# xadow-3-Axis_Digital_Accelerometer_400g.net
KiCad netlist of a schematic drawn in EAGLE
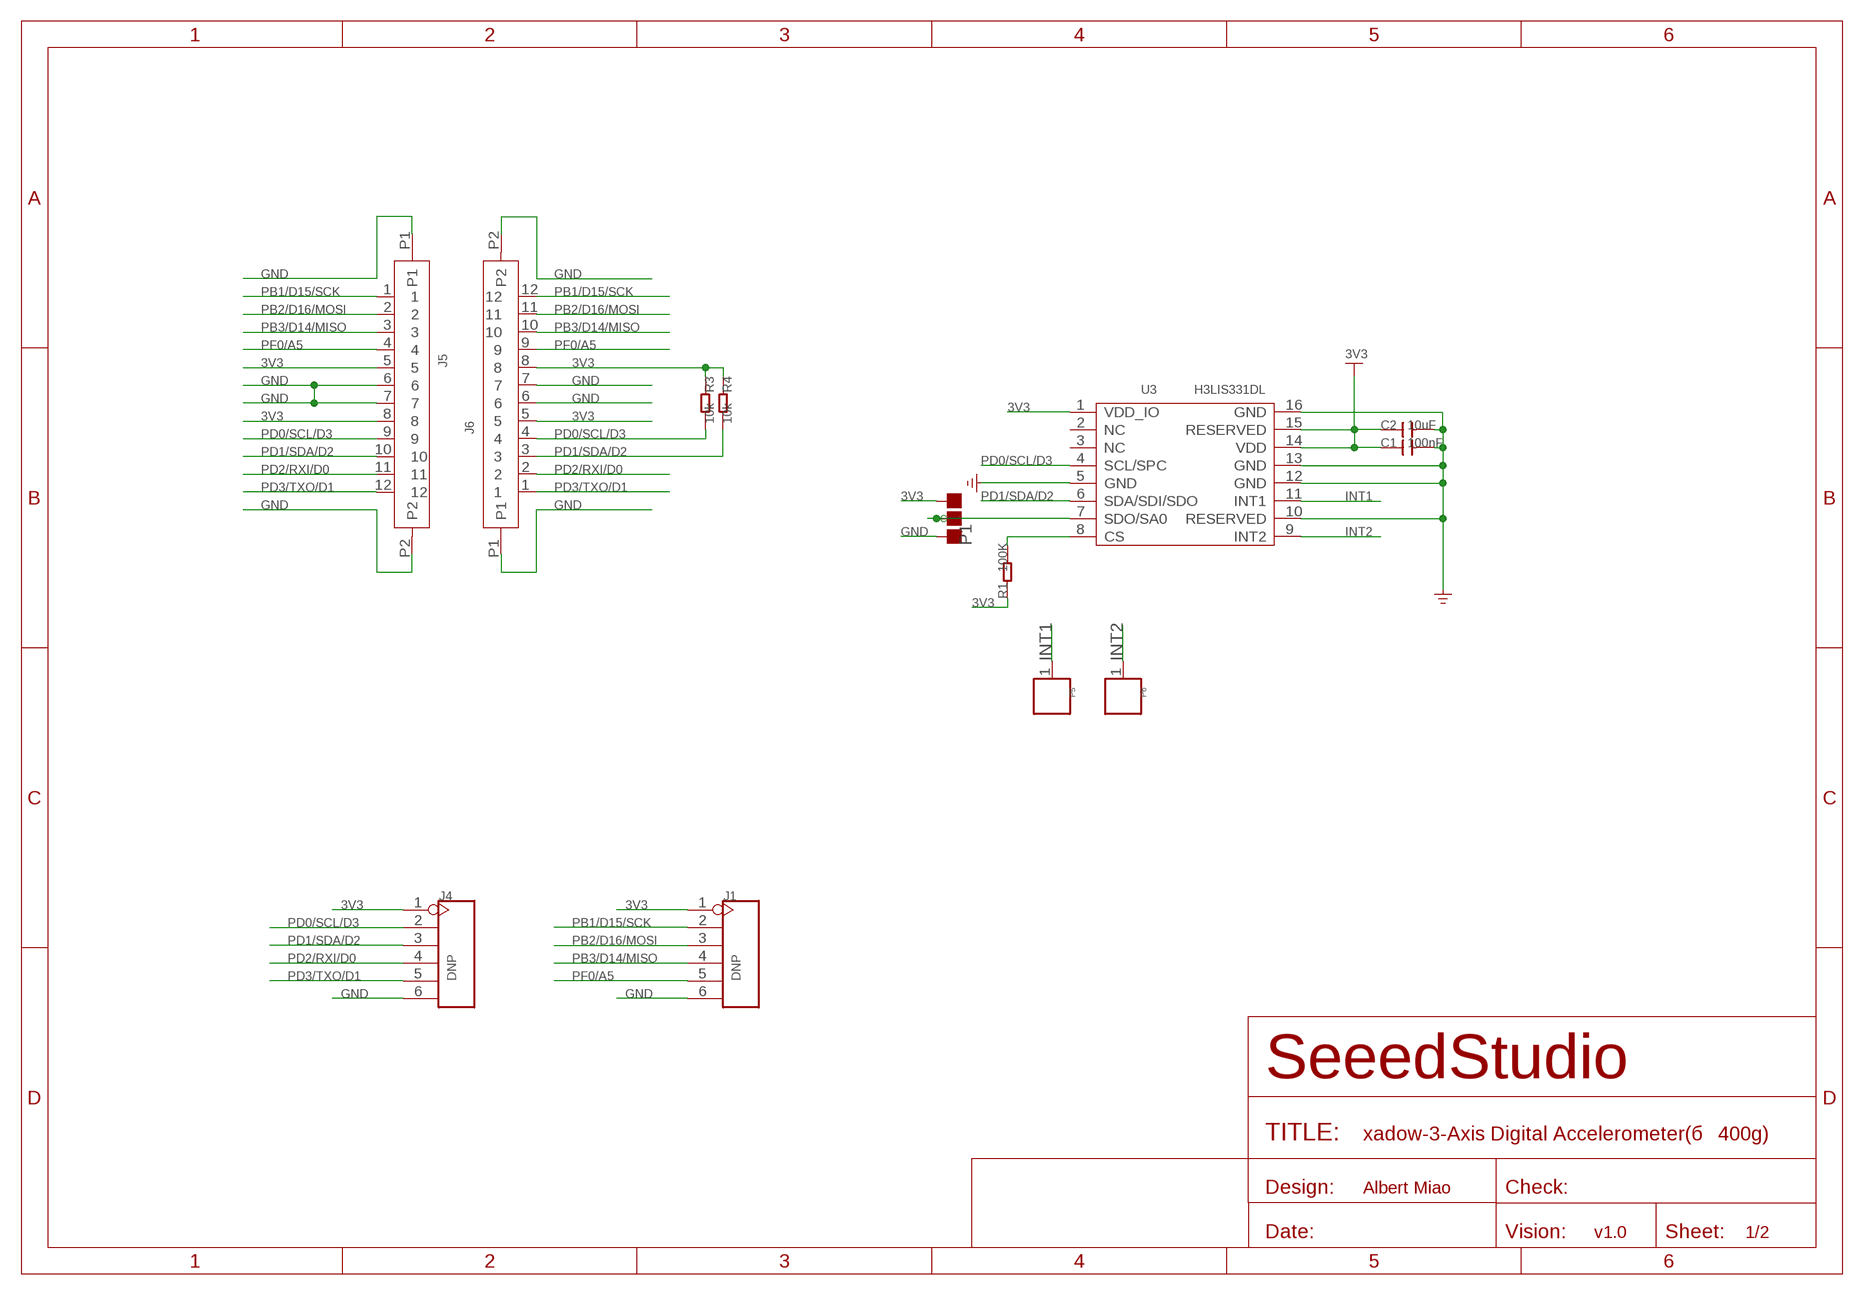
[diagram p0: schematic, sheet 1]
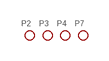
[diagram p1: schematic, sheet 2]

(export (version "E")
  (design (tool "Eeschema 10.0.6"))
  (components
    (comp (ref "C1")
      (value "100nF")
      (footprint "eagle-import:C0603")
      (libsource (lib "eagle-import") (part "C-0603"))
    )
    (comp (ref "C2")
      (value "10uF")
      (footprint "eagle-import:C0805")
      (libsource (lib "eagle-import") (part "C-0805"))
    )
    (comp (ref "J1")
      (value "DNP")
      (footprint "eagle-import:6P-2.54-65_35MIL")
      (libsource (lib "eagle-import") (part "HEADER-6P-65/35MIL"))
    )
    (comp (ref "J4")
      (value "DNP")
      (footprint "eagle-import:6P-2.54-65_35MIL")
      (libsource (lib "eagle-import") (part "HEADER-6P-65/35MIL"))
    )
    (comp (ref "J5")
      (value "FPC052002-12LT-FH12-12S-0.5SH")
      (footprint "eagle-import:12P-0.5-NEW")
      (libsource (lib "eagle-import") (part "FPC052002-12LT-FH12-12S-0.5SH"))
    )
    (comp (ref "J6")
      (value "FPC052002-12LT-FH12-12S-0.5SH")
      (footprint "eagle-import:12P-0.5-NEW")
      (libsource (lib "eagle-import") (part "FPC052002-12LT-FH12-12S-0.5SH"))
    )
    (comp (ref "P1")
      (value "PAD-JUMPER-3P-40*40")
      (footprint "eagle-import:3P-SMD-4.1X1.5")
      (fields (field (name "PARTNO") "DNP"))
      (libsource (lib "eagle-import") (part "PAD-JUMPER-3P-4040"))
    )
    (comp (ref "P5")
      (value "PAD'60/30'")
      (footprint "eagle-import:1P-65_35MIL")
      (libsource (lib "eagle-import") (part "PAD'60/30'"))
    )
    (comp (ref "P6")
      (value "PAD'60/30'")
      (footprint "eagle-import:1P-65_35MIL")
      (libsource (lib "eagle-import") (part "PAD'60/30'"))
    )
    (comp (ref "R1")
      (value "100K")
      (footprint "eagle-import:R0603")
      (libsource (lib "eagle-import") (part "R-0603"))
    )
    (comp (ref "R3")
      (value "10k")
      (footprint "eagle-import:R0603")
      (libsource (lib "eagle-import") (part "R-0603"))
    )
    (comp (ref "R4")
      (value "10k")
      (footprint "eagle-import:R0603")
      (libsource (lib "eagle-import") (part "R-0603"))
    )
    (comp (ref "U3")
      (value "H3LIS331DL")
      (footprint "eagle-import:TFLGA-16")
      (libsource (lib "eagle-import") (part "H3LIS331DL"))
    )
    (comp (ref "P2")
      (value "PAD-MARK")
      (footprint "eagle-import:ROUND-MARK-1.0")
      (fields (field (name "PARTNO") "DNP"))
      (libsource (lib "eagle-import") (part "PAD-MARK"))
    )
    (comp (ref "P3")
      (value "PAD-MARK")
      (footprint "eagle-import:ROUND-MARK-1.0")
      (fields (field (name "PARTNO") "DNP"))
      (libsource (lib "eagle-import") (part "PAD-MARK"))
    )
    (comp (ref "P4")
      (value "PAD-MARK")
      (footprint "eagle-import:ROUND-MARK-1.0")
      (fields (field (name "PARTNO") "DNP"))
      (libsource (lib "eagle-import") (part "PAD-MARK"))
    )
    (comp (ref "P7")
      (value "PAD-MARK")
      (footprint "eagle-import:ROUND-MARK-1.0")
      (fields (field (name "PARTNO") "DNP"))
      (libsource (lib "eagle-import") (part "PAD-MARK"))
    )
  )
  (nets
    (net (code "1") (name "3V3") (class "Default")
      (node (ref "C1") (pin "1") (pinfunction "1_1") (pintype "passive"))
      (node (ref "C2") (pin "1") (pinfunction "1_1") (pintype "passive"))
      (node (ref "J1") (pin "1") (pinfunction "1_1") (pintype "bidirectional"))
      (node (ref "J4") (pin "1") (pinfunction "1_1") (pintype "bidirectional"))
      (node (ref "J5") (pin "5") (pinfunction "5_5") (pintype "bidirectional"))
      (node (ref "J5") (pin "8") (pinfunction "8_8") (pintype "bidirectional"))
      (node (ref "J6") (pin "5") (pinfunction "5_5") (pintype "bidirectional"))
      (node (ref "J6") (pin "8") (pinfunction "8_8") (pintype "bidirectional"))
      (node (ref "P1") (pin "00") (pinfunction "L_00") (pintype "bidirectional"))
      (node (ref "R1") (pin "1") (pinfunction "1_1") (pintype "passive"))
      (node (ref "R3") (pin "1") (pinfunction "1_1") (pintype "passive"))
      (node (ref "R4") (pin "1") (pinfunction "1_1") (pintype "passive"))
      (node (ref "U3") (pin "1") (pinfunction "VDD_IO_1") (pintype "bidirectional"))
      (node (ref "U3") (pin "14") (pinfunction "VDD_14") (pintype "bidirectional"))
      (node (ref "U3") (pin "15") (pinfunction "RESERVED_15") (pintype "bidirectional"))
    )
    (net (code "2") (name "GND") (class "Default")
      (node (ref "C1") (pin "2") (pinfunction "2_2") (pintype "passive"))
      (node (ref "C2") (pin "2") (pinfunction "2_2") (pintype "passive"))
      (node (ref "J1") (pin "6") (pinfunction "6_6") (pintype "bidirectional"))
      (node (ref "J4") (pin "6") (pinfunction "6_6") (pintype "bidirectional"))
      (node (ref "J5") (pin "6") (pinfunction "6_6") (pintype "bidirectional"))
      (node (ref "J5") (pin "7") (pinfunction "7_7") (pintype "bidirectional"))
      (node (ref "J5") (pin "P1") (pinfunction "P1_P1") (pintype "bidirectional"))
      (node (ref "J5") (pin "P2") (pinfunction "P2_P2") (pintype "bidirectional"))
      (node (ref "J6") (pin "6") (pinfunction "6_6") (pintype "bidirectional"))
      (node (ref "J6") (pin "7") (pinfunction "7_7") (pintype "bidirectional"))
      (node (ref "J6") (pin "P1") (pinfunction "P1_P1") (pintype "bidirectional"))
      (node (ref "J6") (pin "P2") (pinfunction "P2_P2") (pintype "bidirectional"))
      (node (ref "P1") (pin "11") (pinfunction "R_11") (pintype "bidirectional"))
      (node (ref "U3") (pin "10") (pinfunction "RESERVED_10") (pintype "bidirectional"))
      (node (ref "U3") (pin "12") (pinfunction "GND_12") (pintype "bidirectional"))
      (node (ref "U3") (pin "13") (pinfunction "GND_13") (pintype "bidirectional"))
      (node (ref "U3") (pin "16") (pinfunction "GND_16") (pintype "bidirectional"))
      (node (ref "U3") (pin "5") (pinfunction "GND_5") (pintype "bidirectional"))
    )
    (net (code "3") (name "INT1") (class "Default")
      (node (ref "P5") (pin "1") (pinfunction "P$1_1") (pintype "bidirectional"))
      (node (ref "U3") (pin "11") (pinfunction "INT1_11") (pintype "bidirectional"))
    )
    (net (code "4") (name "INT2") (class "Default")
      (node (ref "P6") (pin "1") (pinfunction "P$1_1") (pintype "bidirectional"))
      (node (ref "U3") (pin "9") (pinfunction "INT2_9") (pintype "bidirectional"))
    )
    (net (code "5") (name "Net-(P1-C)") (class "Default")
      (node (ref "P1") (pin "MM") (pinfunction "C_MM") (pintype "bidirectional"))
      (node (ref "U3") (pin "7") (pinfunction "SDO/SA0_7") (pintype "bidirectional"))
    )
    (net (code "6") (name "Net-(U3-CS)") (class "Default")
      (node (ref "R1") (pin "2") (pinfunction "2_2") (pintype "passive"))
      (node (ref "U3") (pin "8") (pinfunction "CS_8") (pintype "bidirectional"))
    )
    (net (code "7") (name "PB1{slash}D15{slash}SCK") (class "Default")
      (node (ref "J1") (pin "2") (pinfunction "2_2") (pintype "bidirectional"))
      (node (ref "J5") (pin "1") (pinfunction "1_1") (pintype "bidirectional"))
      (node (ref "J6") (pin "12") (pinfunction "12_12") (pintype "bidirectional"))
    )
    (net (code "8") (name "PB2{slash}D16{slash}MOSI") (class "Default")
      (node (ref "J1") (pin "3") (pinfunction "3_3") (pintype "bidirectional"))
      (node (ref "J5") (pin "2") (pinfunction "2_2") (pintype "bidirectional"))
      (node (ref "J6") (pin "11") (pinfunction "11_11") (pintype "bidirectional"))
    )
    (net (code "9") (name "PB3{slash}D14{slash}MISO") (class "Default")
      (node (ref "J1") (pin "4") (pinfunction "4_4") (pintype "bidirectional"))
      (node (ref "J5") (pin "3") (pinfunction "3_3") (pintype "bidirectional"))
      (node (ref "J6") (pin "10") (pinfunction "10_10") (pintype "bidirectional"))
    )
    (net (code "10") (name "PD0{slash}SCL{slash}D3") (class "Default")
      (node (ref "J4") (pin "2") (pinfunction "2_2") (pintype "bidirectional"))
      (node (ref "J5") (pin "9") (pinfunction "9_9") (pintype "bidirectional"))
      (node (ref "J6") (pin "4") (pinfunction "4_4") (pintype "bidirectional"))
      (node (ref "R3") (pin "2") (pinfunction "2_2") (pintype "passive"))
      (node (ref "U3") (pin "4") (pinfunction "SCL/SPC_4") (pintype "bidirectional"))
    )
    (net (code "11") (name "PD1{slash}SDA{slash}D2") (class "Default")
      (node (ref "J4") (pin "3") (pinfunction "3_3") (pintype "bidirectional"))
      (node (ref "J5") (pin "10") (pinfunction "10_10") (pintype "bidirectional"))
      (node (ref "J6") (pin "3") (pinfunction "3_3") (pintype "bidirectional"))
      (node (ref "R4") (pin "2") (pinfunction "2_2") (pintype "passive"))
      (node (ref "U3") (pin "6") (pinfunction "SDA/SDI/SDO_6") (pintype "bidirectional"))
    )
    (net (code "12") (name "PD2{slash}RXI{slash}D0") (class "Default")
      (node (ref "J4") (pin "4") (pinfunction "4_4") (pintype "bidirectional"))
      (node (ref "J5") (pin "11") (pinfunction "11_11") (pintype "bidirectional"))
      (node (ref "J6") (pin "2") (pinfunction "2_2") (pintype "bidirectional"))
    )
    (net (code "13") (name "PD3{slash}TXO{slash}D1") (class "Default")
      (node (ref "J4") (pin "5") (pinfunction "5_5") (pintype "bidirectional"))
      (node (ref "J5") (pin "12") (pinfunction "12_12") (pintype "bidirectional"))
      (node (ref "J6") (pin "1") (pinfunction "1_1") (pintype "bidirectional"))
    )
    (net (code "14") (name "PF0{slash}A5") (class "Default")
      (node (ref "J1") (pin "5") (pinfunction "5_5") (pintype "bidirectional"))
      (node (ref "J5") (pin "4") (pinfunction "4_4") (pintype "bidirectional"))
      (node (ref "J6") (pin "9") (pinfunction "9_9") (pintype "bidirectional"))
    )
    (net (code "15") (name "unconnected-(U3-NC-Pad2)") (class "Default")
      (node (ref "U3") (pin "2") (pinfunction "NC_2") (pintype "bidirectional"))
    )
    (net (code "16") (name "unconnected-(U3-NC-Pad3)") (class "Default")
      (node (ref "U3") (pin "3") (pinfunction "NC_3") (pintype "bidirectional"))
    )
  )
)
